# Flight_Controller_Auxiliary_Board.net
KiCad netlist of a schematic drawn in EAGLE
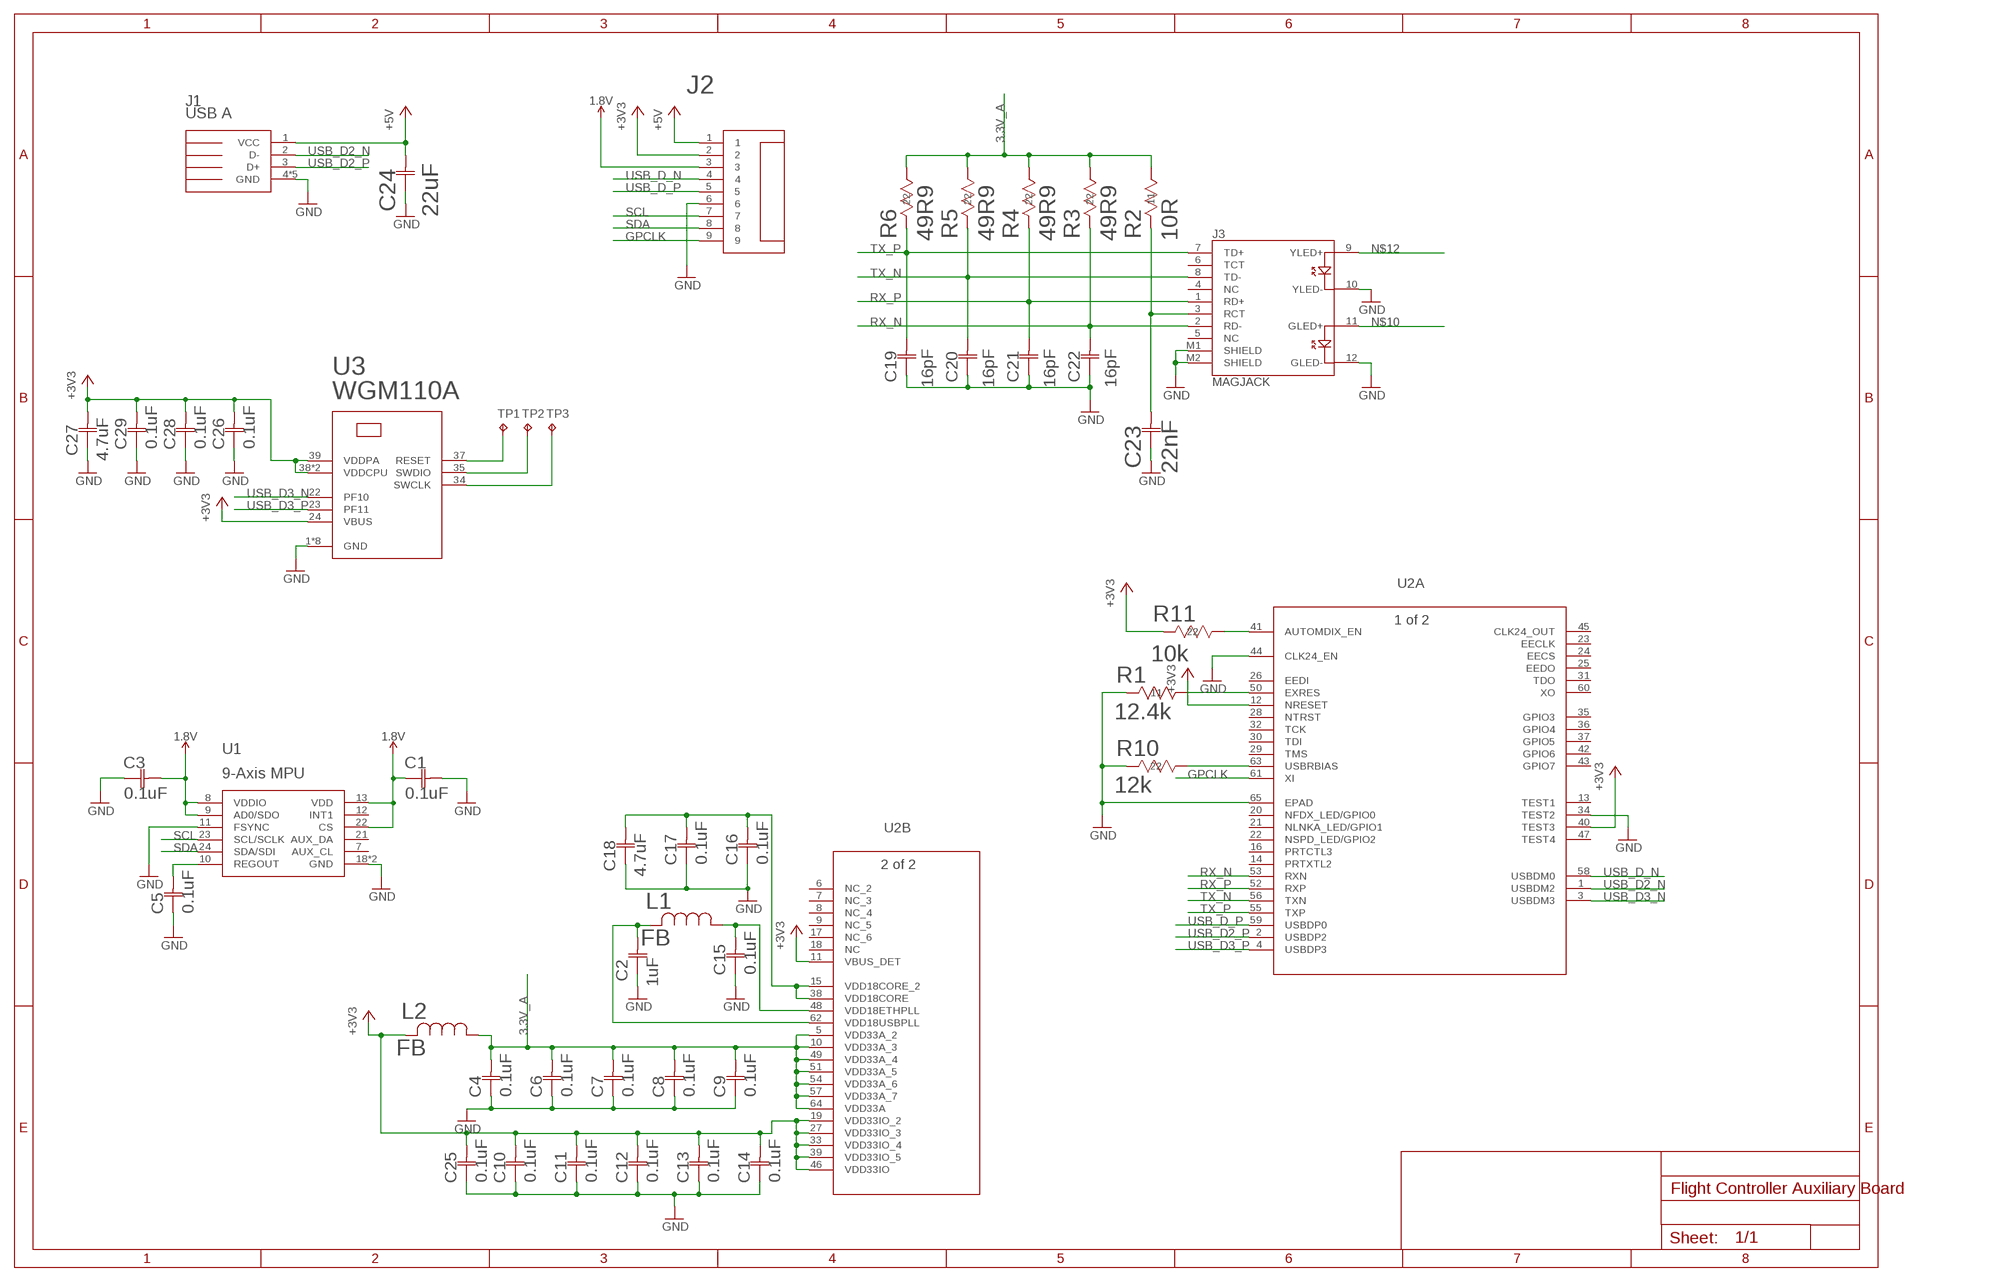
[diagram p0: schematic, sheet 1]

(export (version "E")
  (design (tool "Eeschema 10.0.6"))
  (components
    (comp (ref "C1")
      (value "0.1uF")
      (footprint "eagle-import:0402-M")
      (fields (field (name "MANUFACTURER_PART_NUMBER") "0402ZD104KAT2A"))
      (libsource (lib "eagle-import") (part "0402ZD104KAT2A0402-M"))
    )
    (comp (ref "C2")
      (value "1uF")
      (footprint "eagle-import:YAG_CC0805")
      (fields
        (field (name "MANUFACTURER_PART_NUMBER") "CC0805KKX7R7BB105")
        (field (name "COPYRIGHT") "Copyright C 2015 Accelerated Designs. All rights reserved")
      )
      (libsource (lib "eagle-import") (part "CC0805KKX7R7BB105"))
    )
    (comp (ref "C3")
      (value "0.1uF")
      (footprint "eagle-import:0402-M")
      (fields (field (name "MANUFACTURER_PART_NUMBER") "0402ZD104KAT2A"))
      (libsource (lib "eagle-import") (part "0402ZD104KAT2A0402-M"))
    )
    (comp (ref "C4")
      (value "0.1uF")
      (footprint "eagle-import:0402-M")
      (fields (field (name "MANUFACTURER_PART_NUMBER") "0402ZD104KAT2A"))
      (libsource (lib "eagle-import") (part "0402ZD104KAT2A0402-M"))
    )
    (comp (ref "C5")
      (value "0.1uF")
      (footprint "eagle-import:0402-M")
      (fields (field (name "MANUFACTURER_PART_NUMBER") "0402ZD104KAT2A"))
      (libsource (lib "eagle-import") (part "0402ZD104KAT2A0402-M"))
    )
    (comp (ref "C6")
      (value "0.1uF")
      (footprint "eagle-import:0402-M")
      (fields (field (name "MANUFACTURER_PART_NUMBER") "0402ZD104KAT2A"))
      (libsource (lib "eagle-import") (part "0402ZD104KAT2A0402-M"))
    )
    (comp (ref "C7")
      (value "0.1uF")
      (footprint "eagle-import:0402-M")
      (fields (field (name "MANUFACTURER_PART_NUMBER") "0402ZD104KAT2A"))
      (libsource (lib "eagle-import") (part "0402ZD104KAT2A0402-M"))
    )
    (comp (ref "C8")
      (value "0.1uF")
      (footprint "eagle-import:0402-M")
      (fields (field (name "MANUFACTURER_PART_NUMBER") "0402ZD104KAT2A"))
      (libsource (lib "eagle-import") (part "0402ZD104KAT2A0402-M"))
    )
    (comp (ref "C9")
      (value "0.1uF")
      (footprint "eagle-import:0402-M")
      (fields (field (name "MANUFACTURER_PART_NUMBER") "0402ZD104KAT2A"))
      (libsource (lib "eagle-import") (part "0402ZD104KAT2A0402-M"))
    )
    (comp (ref "C10")
      (value "0.1uF")
      (footprint "eagle-import:0402-M")
      (fields (field (name "MANUFACTURER_PART_NUMBER") "0402ZD104KAT2A"))
      (libsource (lib "eagle-import") (part "0402ZD104KAT2A0402-M"))
    )
    (comp (ref "C11")
      (value "0.1uF")
      (footprint "eagle-import:0402-M")
      (fields (field (name "MANUFACTURER_PART_NUMBER") "0402ZD104KAT2A"))
      (libsource (lib "eagle-import") (part "0402ZD104KAT2A0402-M"))
    )
    (comp (ref "C12")
      (value "0.1uF")
      (footprint "eagle-import:0402-M")
      (fields (field (name "MANUFACTURER_PART_NUMBER") "0402ZD104KAT2A"))
      (libsource (lib "eagle-import") (part "0402ZD104KAT2A0402-M"))
    )
    (comp (ref "C13")
      (value "0.1uF")
      (footprint "eagle-import:0402-M")
      (fields (field (name "MANUFACTURER_PART_NUMBER") "0402ZD104KAT2A"))
      (libsource (lib "eagle-import") (part "0402ZD104KAT2A0402-M"))
    )
    (comp (ref "C14")
      (value "0.1uF")
      (footprint "eagle-import:0402-M")
      (fields (field (name "MANUFACTURER_PART_NUMBER") "0402ZD104KAT2A"))
      (libsource (lib "eagle-import") (part "0402ZD104KAT2A0402-M"))
    )
    (comp (ref "C15")
      (value "0.1uF")
      (footprint "eagle-import:0402-M")
      (fields (field (name "MANUFACTURER_PART_NUMBER") "0402ZD104KAT2A"))
      (libsource (lib "eagle-import") (part "0402ZD104KAT2A0402-M"))
    )
    (comp (ref "C16")
      (value "0.1uF")
      (footprint "eagle-import:0402-M")
      (fields (field (name "MANUFACTURER_PART_NUMBER") "0402ZD104KAT2A"))
      (libsource (lib "eagle-import") (part "0402ZD104KAT2A0402-M"))
    )
    (comp (ref "C17")
      (value "0.1uF")
      (footprint "eagle-import:0402-M")
      (fields (field (name "MANUFACTURER_PART_NUMBER") "0402ZD104KAT2A"))
      (libsource (lib "eagle-import") (part "0402ZD104KAT2A0402-M"))
    )
    (comp (ref "C18")
      (value "4.7uF")
      (footprint "eagle-import:0603-M")
      (fields (field (name "MANUFACTURER_PART_NUMBER") "06036D475KAT2A"))
      (libsource (lib "eagle-import") (part "06036D475KAT2A0603-M"))
    )
    (comp (ref "C19")
      (value "16pF")
      (footprint "eagle-import:G-155-M")
      (fields (field (name "MANUFACTURER_PART_NUMBER") "GRM1555C1H160JA01D"))
      (libsource (lib "eagle-import") (part "GRM1555C1H160JA01DG-155-M"))
    )
    (comp (ref "C20")
      (value "16pF")
      (footprint "eagle-import:G-155-M")
      (fields (field (name "MANUFACTURER_PART_NUMBER") "GRM1555C1H160JA01D"))
      (libsource (lib "eagle-import") (part "GRM1555C1H160JA01DG-155-M"))
    )
    (comp (ref "C21")
      (value "16pF")
      (footprint "eagle-import:G-155-M")
      (fields (field (name "MANUFACTURER_PART_NUMBER") "GRM1555C1H160JA01D"))
      (libsource (lib "eagle-import") (part "GRM1555C1H160JA01DG-155-M"))
    )
    (comp (ref "C22")
      (value "16pF")
      (footprint "eagle-import:G-155-M")
      (fields (field (name "MANUFACTURER_PART_NUMBER") "GRM1555C1H160JA01D"))
      (libsource (lib "eagle-import") (part "GRM1555C1H160JA01DG-155-M"))
    )
    (comp (ref "C23")
      (value "22nF")
      (footprint "eagle-import:G-155-M")
      (fields (field (name "MANUFACTURER_PART_NUMBER") "GRM155R71H223KA12D"))
      (libsource (lib "eagle-import") (part "GRM155R71H223KA12DG-155-M"))
    )
    (comp (ref "C24")
      (value "22uF")
      (footprint "eagle-import:G-21")
      (fields
        (field (name "MANUFACTURER_PART_NUMBER") "GRM21BR60J226ME39L")
        (field (name "COPYRIGHT") "Copyright C 2015 Accelerated Designs. All rights reserved")
      )
      (libsource (lib "eagle-import") (part "GRM21BR60J226ME39L"))
    )
    (comp (ref "C25")
      (value "0.1uF")
      (footprint "eagle-import:0402-M")
      (fields (field (name "MANUFACTURER_PART_NUMBER") "0402ZD104KAT2A"))
      (libsource (lib "eagle-import") (part "0402ZD104KAT2A0402-M"))
    )
    (comp (ref "C26")
      (value "0.1uF")
      (footprint "eagle-import:0402-M")
      (fields (field (name "MANUFACTURER_PART_NUMBER") "0402ZD104KAT2A"))
      (libsource (lib "eagle-import") (part "0402ZD104KAT2A0402-M"))
    )
    (comp (ref "C27")
      (value "4.7uF")
      (footprint "eagle-import:0603-M")
      (fields (field (name "MANUFACTURER_PART_NUMBER") "06036D475KAT2A"))
      (libsource (lib "eagle-import") (part "06036D475KAT2A0603-M"))
    )
    (comp (ref "C28")
      (value "0.1uF")
      (footprint "eagle-import:0402-M")
      (fields (field (name "MANUFACTURER_PART_NUMBER") "0402ZD104KAT2A"))
      (libsource (lib "eagle-import") (part "0402ZD104KAT2A0402-M"))
    )
    (comp (ref "C29")
      (value "0.1uF")
      (footprint "eagle-import:0402-M")
      (fields (field (name "MANUFACTURER_PART_NUMBER") "0402ZD104KAT2A"))
      (libsource (lib "eagle-import") (part "0402ZD104KAT2A0402-M"))
    )
    (comp (ref "J1")
      (value "USB_A_VERT")
      (footprint "eagle-import:USB_A_VERTICAL")
      (libsource (lib "eagle-import") (part "USB_A_VERT"))
    )
    (comp (ref "J2")
      (value "9POS_FFC_CONNECTOR")
      (footprint "eagle-import:9POS_FFC_CONNECTOR")
      (libsource (lib "eagle-import") (part "9POS_FFC_CONNECTOR"))
    )
    (comp (ref "J3")
      (value "MAGJACK")
      (footprint "eagle-import:MAGJACK")
      (libsource (lib "eagle-import") (part "MAGJACK"))
    )
    (comp (ref "L1")
      (value "FB")
      (footprint "eagle-import:IND_BLM18_0603-M")
      (fields (field (name "MANUFACTURER_PART_NUMBER") "BLM18AG601SN1D"))
      (libsource (lib "eagle-import") (part "BLM18AG601SN1DIND_BLM18_0603-M"))
    )
    (comp (ref "L2")
      (value "FB")
      (footprint "eagle-import:IND_BLM18_0603-M")
      (fields (field (name "MANUFACTURER_PART_NUMBER") "BLM18AG601SN1D"))
      (libsource (lib "eagle-import") (part "BLM18AG601SN1DIND_BLM18_0603-M"))
    )
    (comp (ref "R1")
      (value "12.4k")
      (footprint "eagle-import:YAG_R0402-M")
      (fields (field (name "MANUFACTURER_PART_NUMBER") "RC0402FR0712K4L"))
      (libsource (lib "eagle-import") (part "RC0402FR-0712K4LYAG_R0402-M"))
    )
    (comp (ref "R2")
      (value "10R")
      (footprint "eagle-import:STA_RNCP0805-M")
      (fields
        (field (name "MANUFACTURER_PART_NUMBER") "RNCP0805FTD10R0")
        (field (name "COPYRIGHT") "Copyright C 2015 Accelerated Designs. All rights reserved")
      )
      (libsource (lib "eagle-import") (part "RNCP0805FTD10R0STA_RNCP0805-M"))
    )
    (comp (ref "R3")
      (value "49R9")
      (footprint "eagle-import:RC0402N-M")
      (fields (field (name "MANUFACTURER_PART_NUMBER") "RC0402FR0749K9L"))
      (libsource (lib "eagle-import") (part "RC0402FR-0749K9LRC0402N-M"))
    )
    (comp (ref "R4")
      (value "49R9")
      (footprint "eagle-import:RC0402N-M")
      (fields (field (name "MANUFACTURER_PART_NUMBER") "RC0402FR0749K9L"))
      (libsource (lib "eagle-import") (part "RC0402FR-0749K9LRC0402N-M"))
    )
    (comp (ref "R5")
      (value "49R9")
      (footprint "eagle-import:RC0402N-M")
      (fields (field (name "MANUFACTURER_PART_NUMBER") "RC0402FR0749K9L"))
      (libsource (lib "eagle-import") (part "RC0402FR-0749K9LRC0402N-M"))
    )
    (comp (ref "R6")
      (value "49R9")
      (footprint "eagle-import:RC0402N-M")
      (fields (field (name "MANUFACTURER_PART_NUMBER") "RC0402FR0749K9L"))
      (libsource (lib "eagle-import") (part "RC0402FR-0749K9LRC0402N-M"))
    )
    (comp (ref "R10")
      (value "12k")
      (footprint "eagle-import:RC0402N-M")
      (fields (field (name "MANUFACTURER_PART_NUMBER") "RC0402FR0712KL"))
      (libsource (lib "eagle-import") (part "RC0402FR-0712KLRC0402N-M"))
    )
    (comp (ref "R11")
      (value "10k")
      (footprint "eagle-import:RC0805N")
      (fields
        (field (name "DIGIKEYPARTNUMBER") "P10KDATRND")
        (field (name "MANUFACTURER_PART_NUMBER") "ERA6AEB103V")
        (field (name "TOLERANCE") "0.1%")
        (field (name "COPYRIGHT") "Copyright C 2015 Accelerated Designs. All rights reserved")
      )
      (libsource (lib "eagle-import") (part "ERA-6AEB103V"))
    )
    (comp (ref "TP1")
      (value "TPB2,54")
      (footprint "eagle-import:B2,54")
      (libsource (lib "eagle-import") (part "TPB2,54"))
    )
    (comp (ref "TP2")
      (value "TPB2,54")
      (footprint "eagle-import:B2,54")
      (libsource (lib "eagle-import") (part "TPB2,54"))
    )
    (comp (ref "TP3")
      (value "TPB2,54")
      (footprint "eagle-import:B2,54")
      (libsource (lib "eagle-import") (part "TPB2,54"))
    )
    (comp (ref "U1")
      (value "ICM-20948")
      (footprint "eagle-import:QFN40P300X300X105-25N")
      (libsource (lib "eagle-import") (part "ICM-20948"))
    )
    (comp (ref "U2")
      (value "LAN9512-JZXQFN64_9X9MC-M")
      (footprint "eagle-import:QFN64_9X9MC-M")
      (fields (field (name "MANUFACTURER_PART_NUMBER") "LAN9512JZX"))
      (libsource (lib "eagle-import") (part "LAN9512-JZXQFN64_9X9MC-M"))
    )
    (comp (ref "U3")
      (value "WGM110A")
      (footprint "eagle-import:WGM110A")
      (libsource (lib "eagle-import") (part "WGM110A"))
    )
  )
  (nets
    (net (code "1") (name "+3V3") (class "Default")
      (node (ref "C10") (pin "2") (pinfunction "2_2") (pintype "passive"))
      (node (ref "C11") (pin "2") (pinfunction "2_2") (pintype "passive"))
      (node (ref "C12") (pin "2") (pinfunction "2_2") (pintype "passive"))
      (node (ref "C13") (pin "2") (pinfunction "2_2") (pintype "passive"))
      (node (ref "C14") (pin "2") (pinfunction "2_2") (pintype "passive"))
      (node (ref "C25") (pin "2") (pinfunction "2_2") (pintype "passive"))
      (node (ref "C26") (pin "2") (pinfunction "2_2") (pintype "passive"))
      (node (ref "C27") (pin "2") (pinfunction "2_2") (pintype "passive"))
      (node (ref "C28") (pin "2") (pinfunction "2_2") (pintype "passive"))
      (node (ref "C29") (pin "2") (pinfunction "2_2") (pintype "passive"))
      (node (ref "J2") (pin "2") (pinfunction "2_2") (pintype "bidirectional"))
      (node (ref "L2") (pin "2") (pinfunction "2_2") (pintype "passive"))
      (node (ref "R11") (pin "2") (pinfunction "22_2") (pintype "passive"))
      (node (ref "U2") (pin "11") (pinfunction "VBUS_DET_11") (pintype "power_in"))
      (node (ref "U2") (pin "12") (pinfunction "NRESET_12") (pintype "input"))
      (node (ref "U2") (pin "19") (pinfunction "VDD33IO_2_19") (pintype "power_in"))
      (node (ref "U2") (pin "27") (pinfunction "VDD33IO_3_27") (pintype "power_in"))
      (node (ref "U2") (pin "33") (pinfunction "VDD33IO_4_33") (pintype "power_in"))
      (node (ref "U2") (pin "39") (pinfunction "VDD33IO_5_39") (pintype "power_in"))
      (node (ref "U2") (pin "40") (pinfunction "TEST3_40") (pintype "passive"))
      (node (ref "U2") (pin "46") (pinfunction "VDD33IO_46") (pintype "power_in"))
      (node (ref "U3") (pin "24") (pinfunction "VBUS_24") (pintype "bidirectional"))
      (node (ref "U3") (pin "38") (pinfunction "VDDCPU_38") (pintype "bidirectional"))
      (node (ref "U3") (pin "39") (pinfunction "VDDPA_39") (pintype "bidirectional"))
      (node (ref "U3") (pin "51") (pinfunction "VDDCPU_51") (pintype "bidirectional"))
    )
    (net (code "2") (name "+5V") (class "Default")
      (node (ref "C24") (pin "2") (pinfunction "22_2") (pintype "passive"))
      (node (ref "J1") (pin "1") (pinfunction "VCC_1") (pintype "bidirectional"))
      (node (ref "J2") (pin "1") (pinfunction "1_1") (pintype "bidirectional"))
    )
    (net (code "3") (name "/3.3V_A") (class "Default")
      (node (ref "C4") (pin "2") (pinfunction "2_2") (pintype "passive"))
      (node (ref "C6") (pin "2") (pinfunction "2_2") (pintype "passive"))
      (node (ref "C7") (pin "2") (pinfunction "2_2") (pintype "passive"))
      (node (ref "C8") (pin "2") (pinfunction "2_2") (pintype "passive"))
      (node (ref "C9") (pin "2") (pinfunction "2_2") (pintype "passive"))
      (node (ref "L2") (pin "1") (pinfunction "1_1") (pintype "passive"))
      (node (ref "R2") (pin "2") (pinfunction "22_2") (pintype "passive"))
      (node (ref "R3") (pin "1") (pinfunction "11_1") (pintype "passive"))
      (node (ref "R4") (pin "1") (pinfunction "11_1") (pintype "passive"))
      (node (ref "R5") (pin "1") (pinfunction "11_1") (pintype "passive"))
      (node (ref "R6") (pin "1") (pinfunction "11_1") (pintype "passive"))
      (node (ref "U2") (pin "10") (pinfunction "VDD33A_3_10") (pintype "power_in"))
      (node (ref "U2") (pin "49") (pinfunction "VDD33A_4_49") (pintype "power_in"))
      (node (ref "U2") (pin "5") (pinfunction "VDD33A_2_5") (pintype "power_in"))
      (node (ref "U2") (pin "51") (pinfunction "VDD33A_5_51") (pintype "power_in"))
      (node (ref "U2") (pin "54") (pinfunction "VDD33A_6_54") (pintype "power_in"))
      (node (ref "U2") (pin "57") (pinfunction "VDD33A_7_57") (pintype "power_in"))
      (node (ref "U2") (pin "64") (pinfunction "VDD33A_64") (pintype "power_in"))
    )
    (net (code "4") (name "/GPCLK") (class "Default")
      (node (ref "J2") (pin "9") (pinfunction "9_9") (pintype "bidirectional"))
      (node (ref "U2") (pin "61") (pinfunction "XI_61") (pintype "input"))
    )
    (net (code "5") (name "/N$10") (class "Default")
      (node (ref "J3") (pin "11") (pinfunction "GLED+_11") (pintype "bidirectional"))
    )
    (net (code "6") (name "/N$12") (class "Default")
      (node (ref "J3") (pin "9") (pinfunction "YLED+_9") (pintype "bidirectional"))
    )
    (net (code "7") (name "/RX_N") (class "Default")
      (node (ref "C22") (pin "2") (pinfunction "22_2") (pintype "passive"))
      (node (ref "J3") (pin "2") (pinfunction "RD-_2") (pintype "bidirectional"))
      (node (ref "R3") (pin "2") (pinfunction "22_2") (pintype "passive"))
      (node (ref "U2") (pin "53") (pinfunction "RXN_53") (pintype "bidirectional"))
    )
    (net (code "8") (name "/RX_P") (class "Default")
      (node (ref "C21") (pin "2") (pinfunction "22_2") (pintype "passive"))
      (node (ref "J3") (pin "1") (pinfunction "RD+_1") (pintype "bidirectional"))
      (node (ref "R4") (pin "2") (pinfunction "22_2") (pintype "passive"))
      (node (ref "U2") (pin "52") (pinfunction "RXP_52") (pintype "bidirectional"))
    )
    (net (code "9") (name "/SCL") (class "Default")
      (node (ref "J2") (pin "7") (pinfunction "7_7") (pintype "bidirectional"))
      (node (ref "U1") (pin "23") (pinfunction "SCL/SCLK_23") (pintype "bidirectional"))
    )
    (net (code "10") (name "/SDA") (class "Default")
      (node (ref "J2") (pin "8") (pinfunction "8_8") (pintype "bidirectional"))
      (node (ref "U1") (pin "24") (pinfunction "SDA/SDI_24") (pintype "bidirectional"))
    )
    (net (code "11") (name "/TX_N") (class "Default")
      (node (ref "C20") (pin "2") (pinfunction "22_2") (pintype "passive"))
      (node (ref "J3") (pin "8") (pinfunction "TD-_8") (pintype "bidirectional"))
      (node (ref "R5") (pin "2") (pinfunction "22_2") (pintype "passive"))
      (node (ref "U2") (pin "56") (pinfunction "TXN_56") (pintype "bidirectional"))
    )
    (net (code "12") (name "/TX_P") (class "Default")
      (node (ref "C19") (pin "2") (pinfunction "22_2") (pintype "passive"))
      (node (ref "J3") (pin "7") (pinfunction "TD+_7") (pintype "bidirectional"))
      (node (ref "R6") (pin "2") (pinfunction "22_2") (pintype "passive"))
      (node (ref "U2") (pin "55") (pinfunction "TXP_55") (pintype "bidirectional"))
    )
    (net (code "13") (name "/USB_D2_N") (class "Default")
      (node (ref "J1") (pin "2") (pinfunction "D-_2") (pintype "bidirectional"))
      (node (ref "U2") (pin "1") (pinfunction "USBDM2_1") (pintype "bidirectional"))
    )
    (net (code "14") (name "/USB_D2_P") (class "Default")
      (node (ref "J1") (pin "3") (pinfunction "D+_3") (pintype "bidirectional"))
      (node (ref "U2") (pin "2") (pinfunction "USBDP2_2") (pintype "bidirectional"))
    )
    (net (code "15") (name "/USB_D3_N") (class "Default")
      (node (ref "U2") (pin "3") (pinfunction "USBDM3_3") (pintype "bidirectional"))
      (node (ref "U3") (pin "22") (pinfunction "PF10_22") (pintype "bidirectional"))
    )
    (net (code "16") (name "/USB_D3_P") (class "Default")
      (node (ref "U2") (pin "4") (pinfunction "USBDP3_4") (pintype "bidirectional"))
      (node (ref "U3") (pin "23") (pinfunction "PF11_23") (pintype "bidirectional"))
    )
    (net (code "17") (name "/USB_D_N") (class "Default")
      (node (ref "J2") (pin "4") (pinfunction "4_4") (pintype "bidirectional"))
      (node (ref "U2") (pin "58") (pinfunction "USBDM0_58") (pintype "bidirectional"))
    )
    (net (code "18") (name "/USB_D_P") (class "Default")
      (node (ref "J2") (pin "5") (pinfunction "5_5") (pintype "bidirectional"))
      (node (ref "U2") (pin "59") (pinfunction "USBDP0_59") (pintype "bidirectional"))
    )
    (net (code "19") (name "1.8V") (class "Default")
      (node (ref "C1") (pin "1") (pinfunction "1_1") (pintype "passive"))
      (node (ref "C3") (pin "2") (pinfunction "2_2") (pintype "passive"))
      (node (ref "J2") (pin "3") (pinfunction "3_3") (pintype "bidirectional"))
      (node (ref "U1") (pin "13") (pinfunction "VDD_13") (pintype "bidirectional"))
      (node (ref "U1") (pin "22") (pinfunction "CS_22") (pintype "bidirectional"))
      (node (ref "U1") (pin "8") (pinfunction "VDDIO_8") (pintype "bidirectional"))
      (node (ref "U1") (pin "9") (pinfunction "AD0/SDO_9") (pintype "bidirectional"))
    )
    (net (code "20") (name "GND") (class "Default")
      (node (ref "C1") (pin "2") (pinfunction "2_2") (pintype "passive"))
      (node (ref "C10") (pin "1") (pinfunction "1_1") (pintype "passive"))
      (node (ref "C11") (pin "1") (pinfunction "1_1") (pintype "passive"))
      (node (ref "C12") (pin "1") (pinfunction "1_1") (pintype "passive"))
      (node (ref "C13") (pin "1") (pinfunction "1_1") (pintype "passive"))
      (node (ref "C14") (pin "1") (pinfunction "1_1") (pintype "passive"))
      (node (ref "C15") (pin "1") (pinfunction "1_1") (pintype "passive"))
      (node (ref "C16") (pin "1") (pinfunction "1_1") (pintype "passive"))
      (node (ref "C17") (pin "1") (pinfunction "1_1") (pintype "passive"))
      (node (ref "C18") (pin "1") (pinfunction "1_1") (pintype "passive"))
      (node (ref "C19") (pin "1") (pinfunction "11_1") (pintype "passive"))
      (node (ref "C2") (pin "1") (pinfunction "11_1") (pintype "passive"))
      (node (ref "C20") (pin "1") (pinfunction "11_1") (pintype "passive"))
      (node (ref "C21") (pin "1") (pinfunction "11_1") (pintype "passive"))
      (node (ref "C22") (pin "1") (pinfunction "11_1") (pintype "passive"))
      (node (ref "C23") (pin "1") (pinfunction "11_1") (pintype "passive"))
      (node (ref "C24") (pin "1") (pinfunction "11_1") (pintype "passive"))
      (node (ref "C25") (pin "1") (pinfunction "1_1") (pintype "passive"))
      (node (ref "C26") (pin "1") (pinfunction "1_1") (pintype "passive"))
      (node (ref "C27") (pin "1") (pinfunction "1_1") (pintype "passive"))
      (node (ref "C28") (pin "1") (pinfunction "1_1") (pintype "passive"))
      (node (ref "C29") (pin "1") (pinfunction "1_1") (pintype "passive"))
      (node (ref "C3") (pin "1") (pinfunction "1_1") (pintype "passive"))
      (node (ref "C4") (pin "1") (pinfunction "1_1") (pintype "passive"))
      (node (ref "C5") (pin "1") (pinfunction "1_1") (pintype "passive"))
      (node (ref "C6") (pin "1") (pinfunction "1_1") (pintype "passive"))
      (node (ref "C7") (pin "1") (pinfunction "1_1") (pintype "passive"))
      (node (ref "C8") (pin "1") (pinfunction "1_1") (pintype "passive"))
      (node (ref "C9") (pin "1") (pinfunction "1_1") (pintype "passive"))
      (node (ref "J1") (pin "4") (pinfunction "GND_4") (pintype "bidirectional"))
      (node (ref "J1") (pin "P$5") (pinfunction "GND_P$5") (pintype "bidirectional"))
      (node (ref "J1") (pin "P$6") (pinfunction "GND_P$6") (pintype "bidirectional"))
      (node (ref "J1") (pin "P$7") (pinfunction "GND_P$7") (pintype "bidirectional"))
      (node (ref "J1") (pin "P$8") (pinfunction "GND_P$8") (pintype "bidirectional"))
      (node (ref "J2") (pin "6") (pinfunction "6_6") (pintype "bidirectional"))
      (node (ref "J3") (pin "10") (pinfunction "YLED-_10") (pintype "bidirectional"))
      (node (ref "J3") (pin "12") (pinfunction "GLED-_12") (pintype "bidirectional"))
      (node (ref "J3") (pin "M1") (pinfunction "SHIELD_M1") (pintype "bidirectional"))
      (node (ref "J3") (pin "M2") (pinfunction "SHIELD_M2") (pintype "bidirectional"))
      (node (ref "R1") (pin "1") (pinfunction "11_1") (pintype "passive"))
      (node (ref "R10") (pin "2") (pinfunction "22_2") (pintype "passive"))
      (node (ref "U1") (pin "11") (pinfunction "FSYNC_11") (pintype "bidirectional"))
      (node (ref "U1") (pin "18") (pinfunction "GND_18") (pintype "bidirectional"))
      (node (ref "U1") (pin "20") (pinfunction "GND_20") (pintype "bidirectional"))
      (node (ref "U2") (pin "34") (pinfunction "TEST2_34") (pintype "passive"))
      (node (ref "U2") (pin "44") (pinfunction "CLK24_EN_44") (pintype "input"))
      (node (ref "U2") (pin "65") (pinfunction "EPAD_65") (pintype "passive"))
      (node (ref "U3") (pin "1") (pinfunction "GND_1") (pintype "bidirectional"))
      (node (ref "U3") (pin "16") (pinfunction "GND_16") (pintype "bidirectional"))
      (node (ref "U3") (pin "25") (pinfunction "GND_25") (pintype "bidirectional"))
      (node (ref "U3") (pin "40") (pinfunction "GND_40") (pintype "bidirectional"))
      (node (ref "U3") (pin "42") (pinfunction "GND_42") (pintype "bidirectional"))
      (node (ref "U3") (pin "44") (pinfunction "GND_44") (pintype "bidirectional"))
      (node (ref "U3") (pin "46") (pinfunction "GND_46") (pintype "bidirectional"))
      (node (ref "U3") (pin "48") (pinfunction "GND_48") (pintype "bidirectional"))
    )
    (net (code "21") (name "Net-(C2-22)") (class "Default")
      (node (ref "C2") (pin "2") (pinfunction "22_2") (pintype "passive"))
      (node (ref "L1") (pin "2") (pinfunction "2_2") (pintype "passive"))
      (node (ref "U2") (pin "62") (pinfunction "VDD18USBPLL_62") (pintype "power_in"))
    )
    (net (code "22") (name "Net-(C23-22)") (class "Default")
      (node (ref "C23") (pin "2") (pinfunction "22_2") (pintype "passive"))
      (node (ref "J3") (pin "3") (pinfunction "RCT_3") (pintype "bidirectional"))
      (node (ref "R2") (pin "1") (pinfunction "11_1") (pintype "passive"))
    )
    (net (code "23") (name "Net-(R1-22)") (class "Default")
      (node (ref "R1") (pin "2") (pinfunction "22_2") (pintype "passive"))
      (node (ref "U2") (pin "50") (pinfunction "EXRES_50") (pintype "input"))
    )
    (net (code "24") (name "Net-(R10-11)") (class "Default")
      (node (ref "R10") (pin "1") (pinfunction "11_1") (pintype "passive"))
      (node (ref "U2") (pin "63") (pinfunction "USBRBIAS_63") (pintype "input"))
    )
    (net (code "25") (name "Net-(R11-11)") (class "Default")
      (node (ref "R11") (pin "1") (pinfunction "11_1") (pintype "passive"))
      (node (ref "U2") (pin "41") (pinfunction "AUTOMDIX_EN_41") (pintype "input"))
    )
    (net (code "26") (name "Net-(U1-REGOUT)") (class "Default")
      (node (ref "C5") (pin "2") (pinfunction "2_2") (pintype "passive"))
      (node (ref "U1") (pin "10") (pinfunction "REGOUT_10") (pintype "bidirectional"))
    )
    (net (code "27") (name "Net-(U2B-VDD18CORE)") (class "Default")
      (node (ref "C16") (pin "2") (pinfunction "2_2") (pintype "passive"))
      (node (ref "C17") (pin "2") (pinfunction "2_2") (pintype "passive"))
      (node (ref "C18") (pin "2") (pinfunction "2_2") (pintype "passive"))
      (node (ref "U2") (pin "15") (pinfunction "VDD18CORE_2_15") (pintype "power_in"))
      (node (ref "U2") (pin "38") (pinfunction "VDD18CORE_38") (pintype "power_in"))
    )
    (net (code "28") (name "Net-(U2B-VDD18ETHPLL)") (class "Default")
      (node (ref "C15") (pin "2") (pinfunction "2_2") (pintype "passive"))
      (node (ref "L1") (pin "1") (pinfunction "1_1") (pintype "passive"))
      (node (ref "U2") (pin "48") (pinfunction "VDD18ETHPLL_48") (pintype "power_in"))
    )
    (net (code "29") (name "Net-(U3-RESET)") (class "Default")
      (node (ref "TP1") (pin "TP") (pinfunction "TP_TP") (pintype "input"))
      (node (ref "U3") (pin "37") (pinfunction "RESET_37") (pintype "bidirectional"))
    )
    (net (code "30") (name "Net-(U3-SWCLK)") (class "Default")
      (node (ref "TP3") (pin "TP") (pinfunction "TP_TP") (pintype "input"))
      (node (ref "U3") (pin "34") (pinfunction "SWCLK_34") (pintype "bidirectional"))
    )
    (net (code "31") (name "Net-(U3-SWDIO)") (class "Default")
      (node (ref "TP2") (pin "TP") (pinfunction "TP_TP") (pintype "input"))
      (node (ref "U3") (pin "35") (pinfunction "SWDIO_35") (pintype "bidirectional"))
    )
    (net (code "32") (name "unconnected-(J3-NC-Pad4)") (class "Default")
      (node (ref "J3") (pin "4") (pinfunction "NC_4") (pintype "bidirectional"))
    )
    (net (code "33") (name "unconnected-(J3-NC-Pad5)") (class "Default")
      (node (ref "J3") (pin "5") (pinfunction "NC_5") (pintype "bidirectional"))
    )
    (net (code "34") (name "unconnected-(J3-TCT-Pad6)") (class "Default")
      (node (ref "J3") (pin "6") (pinfunction "TCT_6") (pintype "bidirectional"))
    )
    (net (code "35") (name "unconnected-(U1-AUX_CL-Pad7)") (class "Default")
      (node (ref "U1") (pin "7") (pinfunction "AUX_CL_7") (pintype "bidirectional"))
    )
    (net (code "36") (name "unconnected-(U1-AUX_DA-Pad21)") (class "Default")
      (node (ref "U1") (pin "21") (pinfunction "AUX_DA_21") (pintype "bidirectional"))
    )
    (net (code "37") (name "unconnected-(U1-INT1-Pad12)") (class "Default")
      (node (ref "U1") (pin "12") (pinfunction "INT1_12") (pintype "bidirectional"))
    )
    (net (code "38") (name "unconnected-(U2A-CLK24_OUT-Pad45)") (class "Default")
      (node (ref "U2") (pin "45") (pinfunction "CLK24_OUT_45") (pintype "output"))
    )
    (net (code "39") (name "unconnected-(U2A-EECLK-Pad23)") (class "Default")
      (node (ref "U2") (pin "23") (pinfunction "EECLK_23") (pintype "output"))
    )
    (net (code "40") (name "unconnected-(U2A-EECS-Pad24)") (class "Default")
      (node (ref "U2") (pin "24") (pinfunction "EECS_24") (pintype "output"))
    )
    (net (code "41") (name "unconnected-(U2A-EEDI-Pad26)") (class "Default")
      (node (ref "U2") (pin "26") (pinfunction "EEDI_26") (pintype "input"))
    )
    (net (code "42") (name "unconnected-(U2A-EEDO-Pad25)") (class "Default")
      (node (ref "U2") (pin "25") (pinfunction "EEDO_25") (pintype "output"))
    )
    (net (code "43") (name "unconnected-(U2A-GPIO3-Pad35)") (class "Default")
      (node (ref "U2") (pin "35") (pinfunction "GPIO3_35") (pintype "bidirectional"))
    )
    (net (code "44") (name "unconnected-(U2A-GPIO4-Pad36)") (class "Default")
      (node (ref "U2") (pin "36") (pinfunction "GPIO4_36") (pintype "bidirectional"))
    )
    (net (code "45") (name "unconnected-(U2A-GPIO5-Pad37)") (class "Default")
      (node (ref "U2") (pin "37") (pinfunction "GPIO5_37") (pintype "bidirectional"))
    )
    (net (code "46") (name "unconnected-(U2A-GPIO6-Pad42)") (class "Default")
      (node (ref "U2") (pin "42") (pinfunction "GPIO6_42") (pintype "bidirectional"))
    )
    (net (code "47") (name "unconnected-(U2A-GPIO7-Pad43)") (class "Default")
      (node (ref "U2") (pin "43") (pinfunction "GPIO7_43") (pintype "bidirectional"))
    )
    (net (code "48") (name "unconnected-(U2A-NFDX_LED{slash}GPIO0-Pad20)") (class "Default")
      (node (ref "U2") (pin "20") (pinfunction "NFDX_LED/GPIO0_20") (pintype "bidirectional"))
    )
    (net (code "49") (name "unconnected-(U2A-NLNKA_LED{slash}GPIO1-Pad21)") (class "Default")
      (node (ref "U2") (pin "21") (pinfunction "NLNKA_LED/GPIO1_21") (pintype "bidirectional"))
    )
    (net (code "50") (name "unconnected-(U2A-NSPD_LED{slash}GPIO2-Pad22)") (class "Default")
      (node (ref "U2") (pin "22") (pinfunction "NSPD_LED/GPIO2_22") (pintype "bidirectional"))
    )
    (net (code "51") (name "unconnected-(U2A-NTRST-Pad28)") (class "Default")
      (node (ref "U2") (pin "28") (pinfunction "NTRST_28") (pintype "input"))
    )
    (net (code "52") (name "unconnected-(U2A-PRTCTL3-Pad16)") (class "Default")
      (node (ref "U2") (pin "16") (pinfunction "PRTCTL3_16") (pintype "bidirectional"))
    )
    (net (code "53") (name "unconnected-(U2A-PRTXTL2-Pad14)") (class "Default")
      (node (ref "U2") (pin "14") (pinfunction "PRTXTL2_14") (pintype "bidirectional"))
    )
    (net (code "54") (name "unconnected-(U2A-TCK-Pad32)") (class "Default")
      (node (ref "U2") (pin "32") (pinfunction "TCK_32") (pintype "input"))
    )
    (net (code "55") (name "unconnected-(U2A-TDI-Pad30)") (class "Default")
      (node (ref "U2") (pin "30") (pinfunction "TDI_30") (pintype "input"))
    )
    (net (code "56") (name "unconnected-(U2A-TDO-Pad31)") (class "Default")
      (node (ref "U2") (pin "31") (pinfunction "TDO_31") (pintype "output"))
    )
    (net (code "57") (name "unconnected-(U2A-TEST1-Pad13)") (class "Default")
      (node (ref "U2") (pin "13") (pinfunction "TEST1_13") (pintype "passive"))
    )
    (net (code "58") (name "unconnected-(U2A-TEST4-Pad47)") (class "Default")
      (node (ref "U2") (pin "47") (pinfunction "TEST4_47") (pintype "passive"))
    )
    (net (code "59") (name "unconnected-(U2A-TMS-Pad29)") (class "Default")
      (node (ref "U2") (pin "29") (pinfunction "TMS_29") (pintype "input"))
    )
    (net (code "60") (name "unconnected-(U2A-XO-Pad60)") (class "Default")
      (node (ref "U2") (pin "60") (pinfunction "XO_60") (pintype "output"))
    )
    (net (code "61") (name "unconnected-(U2B-NC-Pad18)") (class "Default")
      (node (ref "U2") (pin "18") (pinfunction "NC_18") (pintype "no_connect"))
    )
    (net (code "62") (name "unconnected-(U2B-NC_2-Pad6)") (class "Default")
      (node (ref "U2") (pin "6") (pinfunction "NC_2_6") (pintype "no_connect"))
    )
    (net (code "63") (name "unconnected-(U2B-NC_3-Pad7)") (class "Default")
      (node (ref "U2") (pin "7") (pinfunction "NC_3_7") (pintype "no_connect"))
    )
    (net (code "64") (name "unconnected-(U2B-NC_4-Pad8)") (class "Default")
      (node (ref "U2") (pin "8") (pinfunction "NC_4_8") (pintype "no_connect"))
    )
    (net (code "65") (name "unconnected-(U2B-NC_5-Pad9)") (class "Default")
      (node (ref "U2") (pin "9") (pinfunction "NC_5_9") (pintype "no_connect"))
    )
    (net (code "66") (name "unconnected-(U2B-NC_6-Pad17)") (class "Default")
      (node (ref "U2") (pin "17") (pinfunction "NC_6_17") (pintype "no_connect"))
    )
  )
)
